# akabeacon_square.net
KiCad netlist of a schematic drawn in EAGLE
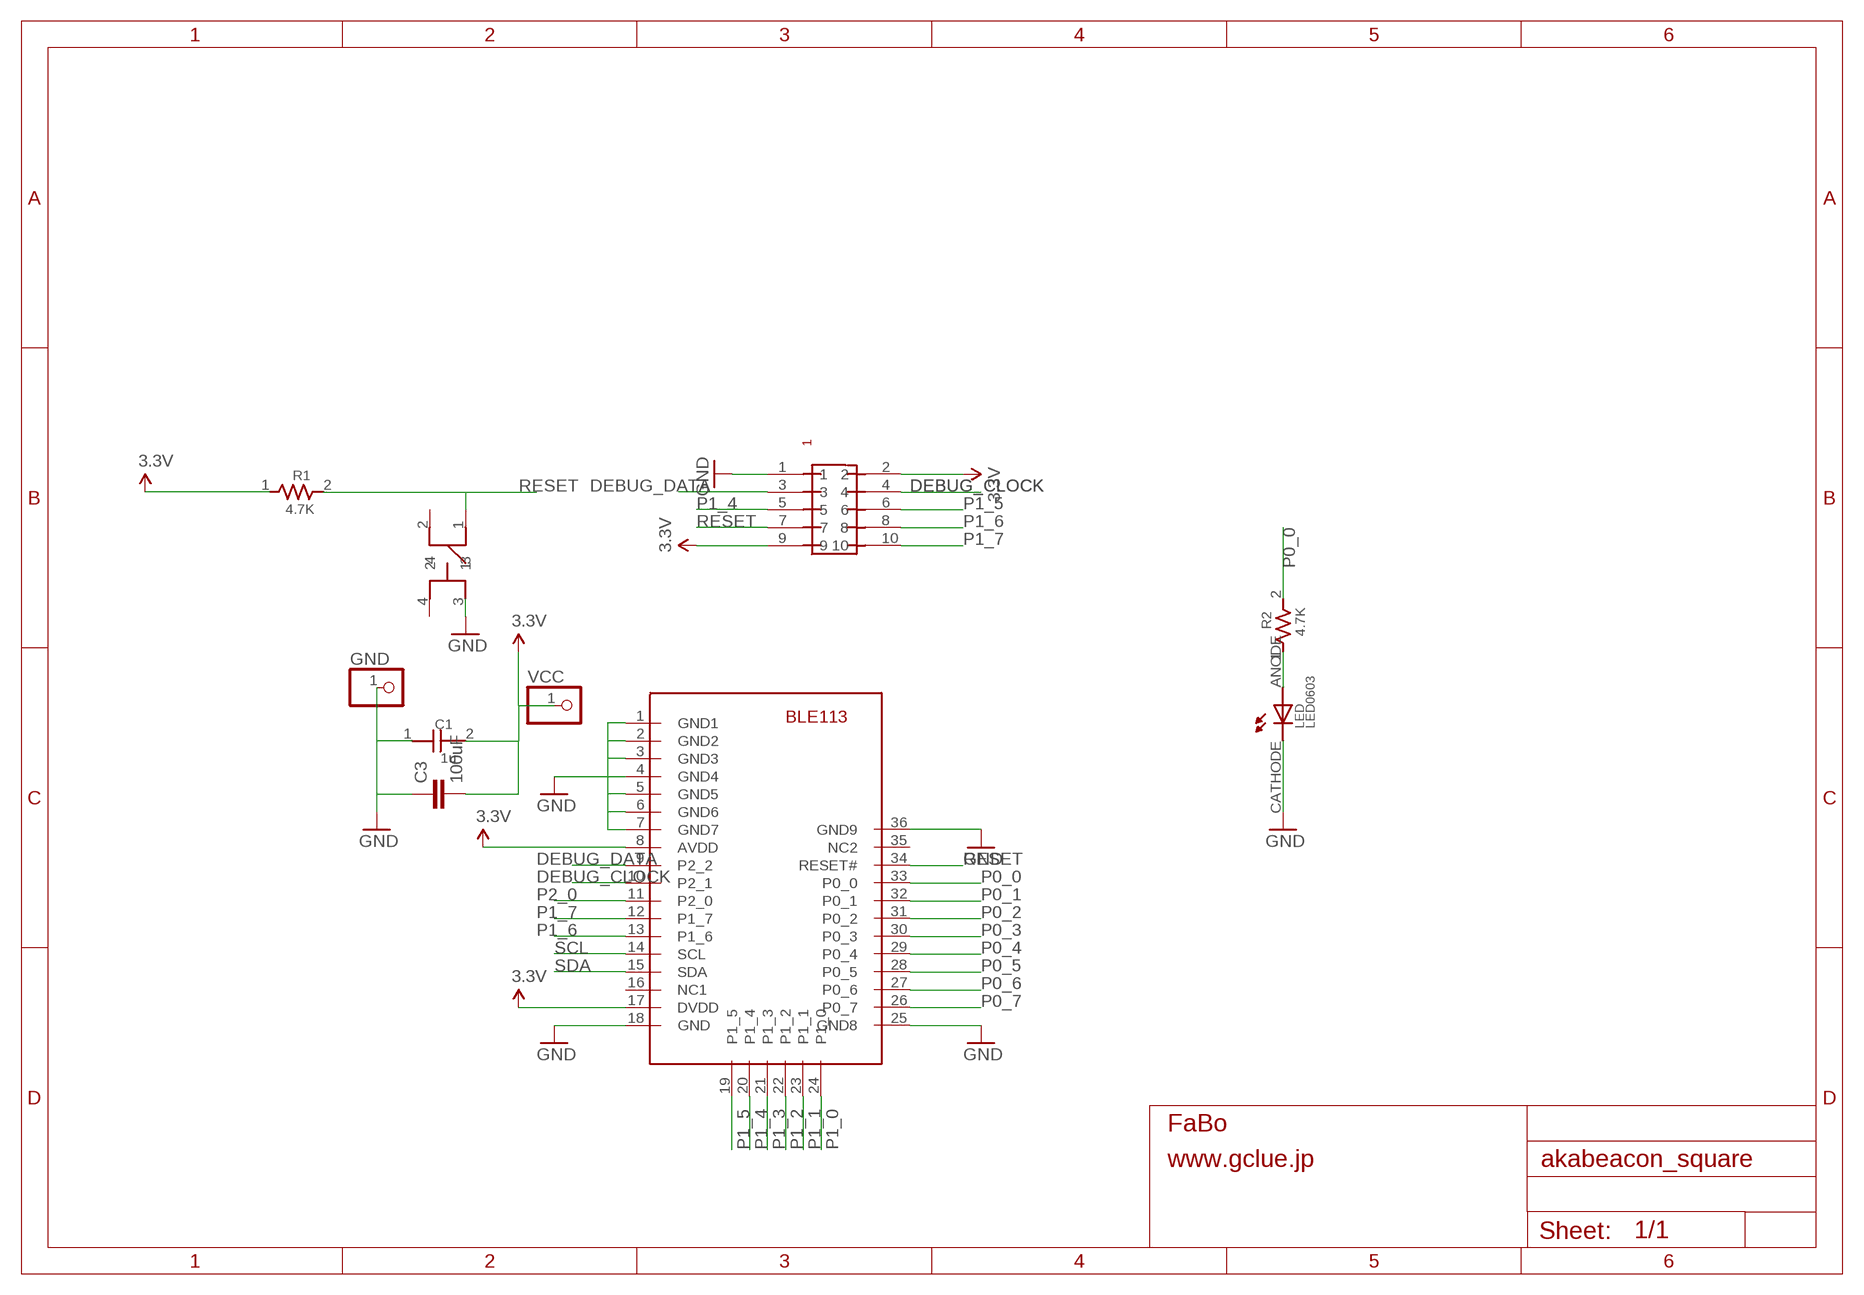
[diagram p0: schematic, sheet 1]

(export (version "E")
  (design (tool "Eeschema 10.0.6"))
  (components
    (comp (ref "C1")
      (value "1u")
      (footprint "eagle-import:0603")
      (libsource (lib "eagle-import") (part "CAPACITOR0603"))
    )
    (comp (ref "C3")
      (value "100uF")
      (footprint "eagle-import:1206")
      (libsource (lib "eagle-import") (part "10UF-6.3V-20%(1206)"))
    )
    (comp (ref "GND")
      (value "PINHD-1X1CB")
      (footprint "eagle-import:1X01-CLEANBIG")
      (libsource (lib "eagle-import") (part "PINHD-1X1CB"))
    )
    (comp (ref "LED")
      (value "LED0603")
      (footprint "eagle-import:0603")
      (libsource (lib "eagle-import") (part "LED0603"))
    )
    (comp (ref "R1")
      (value "4.7K")
      (footprint "eagle-import:0603")
      (libsource (lib "eagle-import") (part "RESISTOR0603"))
    )
    (comp (ref "R2")
      (value "4.7K")
      (footprint "eagle-import:0603")
      (libsource (lib "eagle-import") (part "RESISTOR0603"))
    )
    (comp (ref "U$2")
      (value "PIN-HEADER-SMT(1.27MM)2X5")
      (footprint "eagle-import:PIN-HEADER-SMT(1.27MM)2X5")
      (libsource (lib "eagle-import") (part "PIN-HEADER-SMT(1.27MM)2X5"))
    )
    (comp (ref "U$5")
      (value "BLE113")
      (footprint "eagle-import:BLE113")
      (libsource (lib "eagle-import") (part "BLE113"))
    )
    (comp (ref "U$8")
      (value "SWITCH-LS6J2M-T")
      (footprint "eagle-import:SWICTH-LS6J2M-T")
      (libsource (lib "eagle-import") (part "SWITCH-LS6J2M-T"))
    )
    (comp (ref "VCC")
      (value "PINHD-1X1CB")
      (footprint "eagle-import:1X01-CLEANBIG")
      (libsource (lib "eagle-import") (part "PINHD-1X1CB"))
    )
  )
  (nets
    (net (code "1") (name "/DEBUG_CLOCK") (class "Default")
      (node (ref "U$2") (pin "4") (pinfunction "4_4") (pintype "bidirectional"))
      (node (ref "U$5") (pin "10") (pinfunction "P2_1_10") (pintype "bidirectional"))
    )
    (net (code "2") (name "/DEBUG_DATA") (class "Default")
      (node (ref "U$2") (pin "3") (pinfunction "3_3") (pintype "bidirectional"))
      (node (ref "U$5") (pin "9") (pinfunction "P2_2_9") (pintype "bidirectional"))
    )
    (net (code "3") (name "/P0_0") (class "Default")
      (node (ref "R2") (pin "2") (pinfunction "2_2") (pintype "passive"))
      (node (ref "U$5") (pin "33") (pinfunction "P0_0_33") (pintype "bidirectional"))
    )
    (net (code "4") (name "/P0_1") (class "Default")
      (node (ref "U$5") (pin "32") (pinfunction "P0_1_32") (pintype "bidirectional"))
    )
    (net (code "5") (name "/P0_2") (class "Default")
      (node (ref "U$5") (pin "31") (pinfunction "P0_2_31") (pintype "bidirectional"))
    )
    (net (code "6") (name "/P0_3") (class "Default")
      (node (ref "U$5") (pin "30") (pinfunction "P0_3_30") (pintype "bidirectional"))
    )
    (net (code "7") (name "/P0_4") (class "Default")
      (node (ref "U$5") (pin "29") (pinfunction "P0_4_29") (pintype "bidirectional"))
    )
    (net (code "8") (name "/P0_5") (class "Default")
      (node (ref "U$5") (pin "28") (pinfunction "P0_5_28") (pintype "bidirectional"))
    )
    (net (code "9") (name "/P0_6") (class "Default")
      (node (ref "U$5") (pin "27") (pinfunction "P0_6_27") (pintype "bidirectional"))
    )
    (net (code "10") (name "/P0_7") (class "Default")
      (node (ref "U$5") (pin "26") (pinfunction "P0_7_26") (pintype "bidirectional"))
    )
    (net (code "11") (name "/P1_0") (class "Default")
      (node (ref "U$5") (pin "24") (pinfunction "P1_0_24") (pintype "bidirectional"))
    )
    (net (code "12") (name "/P1_1") (class "Default")
      (node (ref "U$5") (pin "23") (pinfunction "P1_1_23") (pintype "bidirectional"))
    )
    (net (code "13") (name "/P1_2") (class "Default")
      (node (ref "U$5") (pin "22") (pinfunction "P1_2_22") (pintype "bidirectional"))
    )
    (net (code "14") (name "/P1_3") (class "Default")
      (node (ref "U$5") (pin "21") (pinfunction "P1_3_21") (pintype "bidirectional"))
    )
    (net (code "15") (name "/P1_4") (class "Default")
      (node (ref "U$2") (pin "5") (pinfunction "5_5") (pintype "bidirectional"))
      (node (ref "U$5") (pin "20") (pinfunction "P1_4_20") (pintype "bidirectional"))
    )
    (net (code "16") (name "/P1_5") (class "Default")
      (node (ref "U$2") (pin "6") (pinfunction "6_6") (pintype "bidirectional"))
      (node (ref "U$5") (pin "19") (pinfunction "P1_5_19") (pintype "bidirectional"))
    )
    (net (code "17") (name "/P1_6") (class "Default")
      (node (ref "U$2") (pin "8") (pinfunction "8_8") (pintype "bidirectional"))
      (node (ref "U$5") (pin "13") (pinfunction "P1_6_13") (pintype "bidirectional"))
    )
    (net (code "18") (name "/P1_7") (class "Default")
      (node (ref "U$2") (pin "10") (pinfunction "10_10") (pintype "bidirectional"))
      (node (ref "U$5") (pin "12") (pinfunction "P1_7_12") (pintype "bidirectional"))
    )
    (net (code "19") (name "/P2_0") (class "Default")
      (node (ref "U$5") (pin "11") (pinfunction "P2_0_11") (pintype "bidirectional"))
    )
    (net (code "20") (name "/RESET") (class "Default")
      (node (ref "R1") (pin "2") (pinfunction "2_2") (pintype "passive"))
      (node (ref "U$2") (pin "7") (pinfunction "7_7") (pintype "bidirectional"))
      (node (ref "U$5") (pin "34") (pinfunction "RESET#_34") (pintype "bidirectional"))
      (node (ref "U$8") (pin "1") (pinfunction "1_1") (pintype "bidirectional"))
    )
    (net (code "21") (name "/SCL") (class "Default")
      (node (ref "U$5") (pin "14") (pinfunction "SCL_14") (pintype "bidirectional"))
    )
    (net (code "22") (name "/SDA") (class "Default")
      (node (ref "U$5") (pin "15") (pinfunction "SDA_15") (pintype "bidirectional"))
    )
    (net (code "23") (name "3.3V") (class "Default")
      (node (ref "C1") (pin "2") (pinfunction "2_2") (pintype "passive"))
      (node (ref "C3") (pin "2") (pinfunction "2_2") (pintype "passive"))
      (node (ref "R1") (pin "1") (pinfunction "1_1") (pintype "passive"))
      (node (ref "U$2") (pin "2") (pinfunction "2_2") (pintype "bidirectional"))
      (node (ref "U$2") (pin "9") (pinfunction "9_9") (pintype "bidirectional"))
      (node (ref "U$5") (pin "17") (pinfunction "DVDD_17") (pintype "bidirectional"))
      (node (ref "U$5") (pin "8") (pinfunction "AVDD_8") (pintype "bidirectional"))
      (node (ref "VCC") (pin "1") (pinfunction "1_1") (pintype "passive"))
    )
    (net (code "24") (name "GND") (class "Default")
      (node (ref "C1") (pin "1") (pinfunction "1_1") (pintype "passive"))
      (node (ref "C3") (pin "1") (pinfunction "1_1") (pintype "passive"))
      (node (ref "GND") (pin "1") (pinfunction "1_1") (pintype "passive"))
      (node (ref "LED") (pin "CATHODE") (pinfunction "CATHODE_CATHODE") (pintype "passive"))
      (node (ref "U$2") (pin "1") (pinfunction "1_1") (pintype "bidirectional"))
      (node (ref "U$5") (pin "1") (pinfunction "GND1_1") (pintype "bidirectional"))
      (node (ref "U$5") (pin "18") (pinfunction "GND_18") (pintype "bidirectional"))
      (node (ref "U$5") (pin "2") (pinfunction "GND2_2") (pintype "bidirectional"))
      (node (ref "U$5") (pin "25") (pinfunction "GND8_25") (pintype "bidirectional"))
      (node (ref "U$5") (pin "3") (pinfunction "GND3_3") (pintype "bidirectional"))
      (node (ref "U$5") (pin "36") (pinfunction "GND9_36") (pintype "bidirectional"))
      (node (ref "U$5") (pin "4") (pinfunction "GND4_4") (pintype "bidirectional"))
      (node (ref "U$5") (pin "5") (pinfunction "GND5_5") (pintype "bidirectional"))
      (node (ref "U$5") (pin "6") (pinfunction "GND6_6") (pintype "bidirectional"))
      (node (ref "U$5") (pin "7") (pinfunction "GND7_7") (pintype "bidirectional"))
      (node (ref "U$8") (pin "3") (pinfunction "3_3") (pintype "bidirectional"))
    )
    (net (code "25") (name "Net-(LED-PadANODE)") (class "Default")
      (node (ref "LED") (pin "ANODE") (pinfunction "ANODE_ANODE") (pintype "passive"))
      (node (ref "R2") (pin "1") (pinfunction "1_1") (pintype "passive"))
    )
    (net (code "26") (name "unconnected-(U$5-NC1-Pad16)") (class "Default")
      (node (ref "U$5") (pin "16") (pinfunction "NC1_16") (pintype "bidirectional"))
    )
    (net (code "27") (name "unconnected-(U$5-NC2-Pad35)") (class "Default")
      (node (ref "U$5") (pin "35") (pinfunction "NC2_35") (pintype "bidirectional"))
    )
    (net (code "28") (name "unconnected-(U$8-Pad2)") (class "Default")
      (node (ref "U$8") (pin "2") (pinfunction "2_2") (pintype "bidirectional"))
    )
    (net (code "29") (name "unconnected-(U$8-Pad4)") (class "Default")
      (node (ref "U$8") (pin "4") (pinfunction "4_4") (pintype "bidirectional"))
    )
  )
)
